# metercam.net
KiCad netlist of a schematic drawn in EAGLE
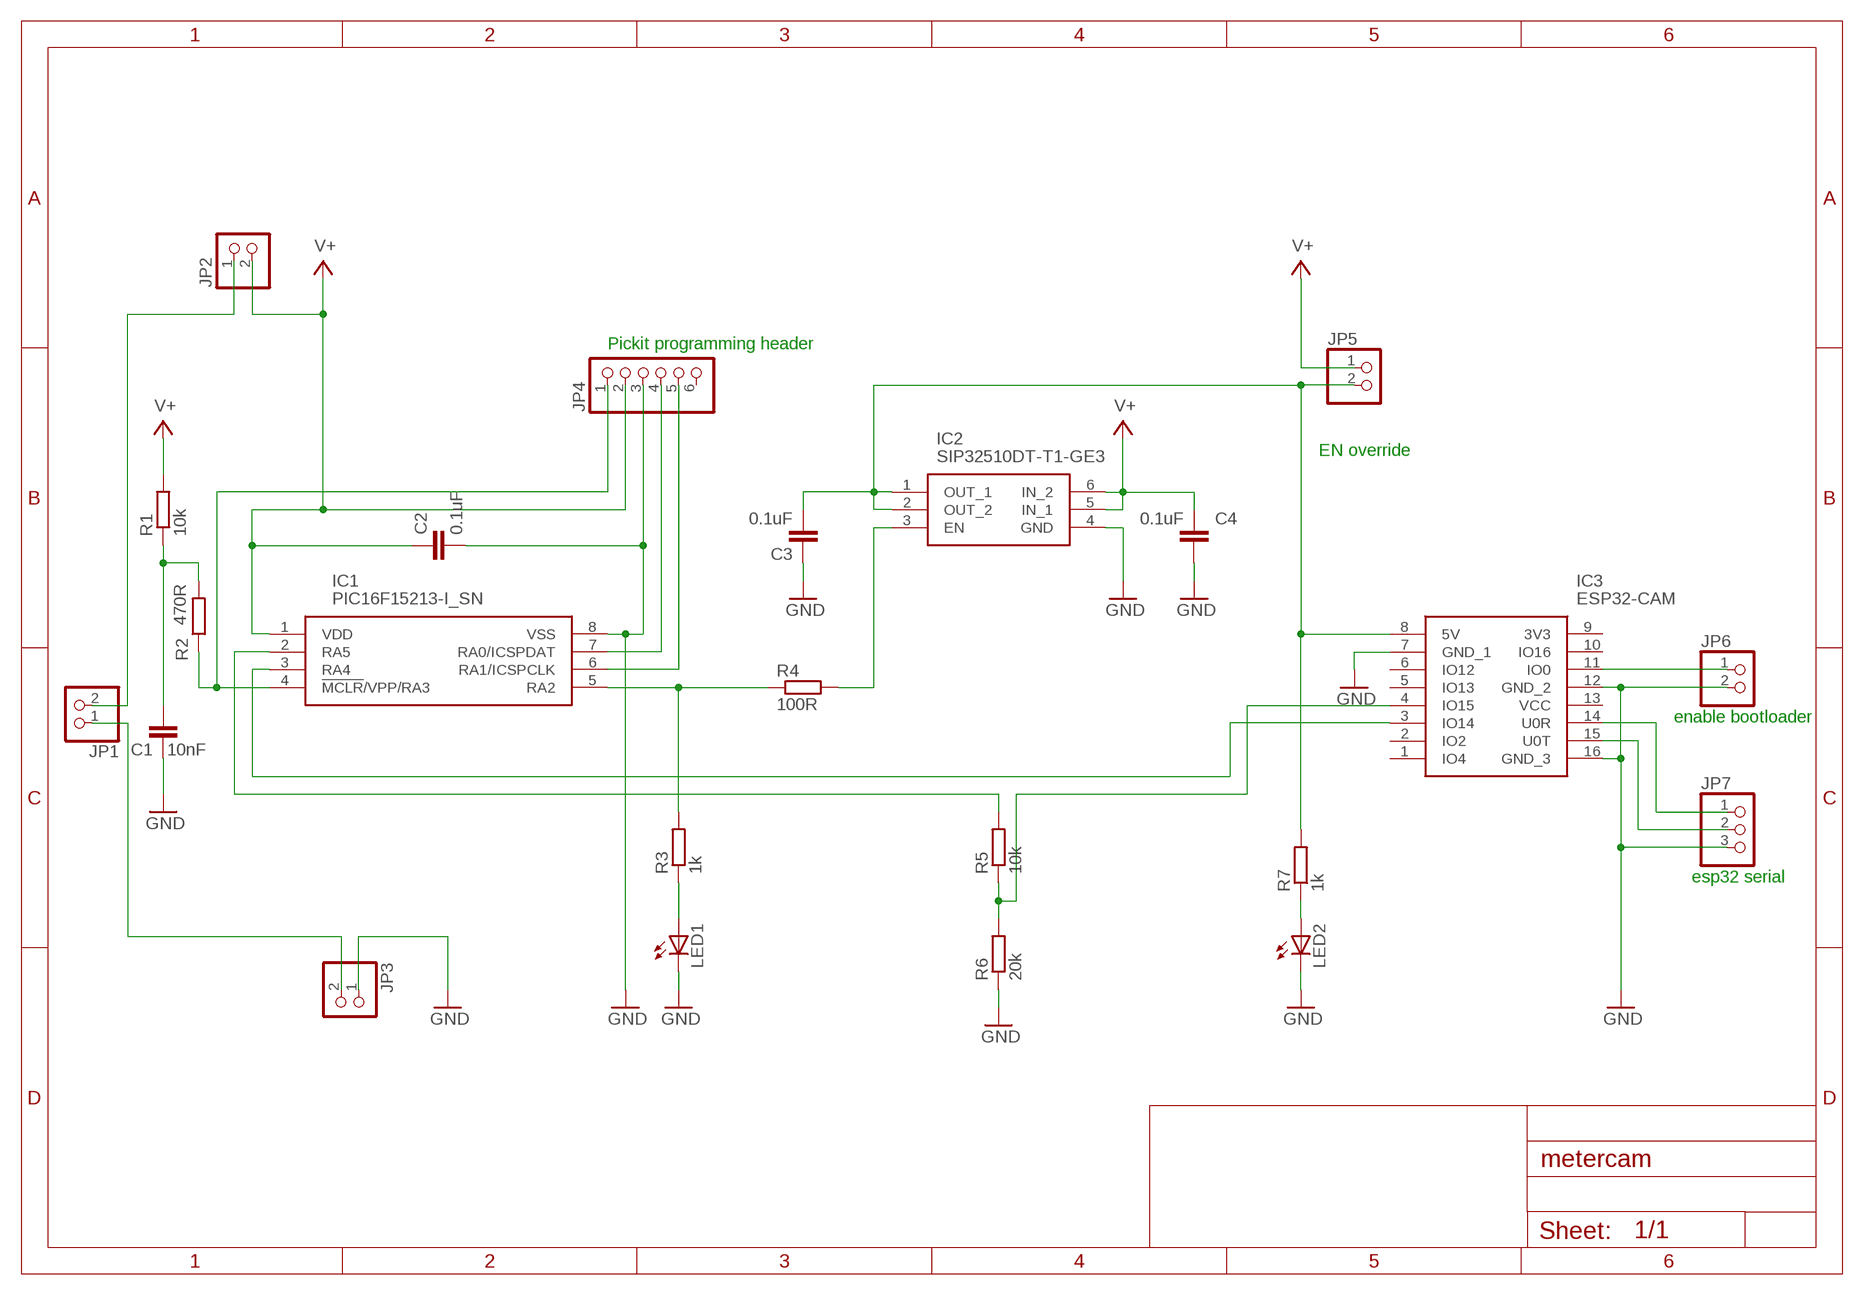
[diagram p0: schematic, sheet 1]

(export (version "E")
  (design (tool "Eeschema 10.0.6"))
  (components
    (comp (ref "C1")
      (value "10nF")
      (footprint "eagle-import:C0805")
      (libsource (lib "eagle-import") (part "C-EUC0805"))
    )
    (comp (ref "C2")
      (value "0.1uF")
      (footprint "eagle-import:C0805")
      (libsource (lib "eagle-import") (part "C-EUC0805"))
    )
    (comp (ref "C3")
      (value "0.1uF")
      (footprint "eagle-import:C0805")
      (libsource (lib "eagle-import") (part "C-EUC0805"))
    )
    (comp (ref "C4")
      (value "0.1uF")
      (footprint "eagle-import:C0805")
      (libsource (lib "eagle-import") (part "C-EUC0805"))
    )
    (comp (ref "IC1")
      (value "PIC16F15213-I_SN")
      (footprint "eagle-import:SOIC127P600X175-8N")
      (fields
        (field (name "MANUFACTURER_PART_NUMBER") "PIC16F15213-I/SN")
        (field (name "MOUSER_PART_NUMBER") "579-PIC16F15213-I/SN")
      )
      (libsource (lib "eagle-import") (part "PIC16F15213-I_SN"))
    )
    (comp (ref "IC2")
      (value "SIP32510DT-T1-GE3")
      (footprint "eagle-import:SOT95P284X110-6N")
      (fields (field (name "MOUSER_PART_NUMBER") "78-SIP32510DT-T1-GE3"))
      (libsource (lib "eagle-import") (part "SIP32510DT-T1-GE3"))
    )
    (comp (ref "IC3")
      (value "ESP32-CAM")
      (footprint "eagle-import:ESP32CAM")
      (libsource (lib "eagle-import") (part "ESP32-CAM"))
    )
    (comp (ref "JP1")
      (value "PINHD-1X2")
      (footprint "eagle-import:1X02")
      (libsource (lib "eagle-import") (part "PINHD-1X2"))
    )
    (comp (ref "JP2")
      (value "PINHD-1X2")
      (footprint "eagle-import:1X02")
      (libsource (lib "eagle-import") (part "PINHD-1X2"))
    )
    (comp (ref "JP3")
      (value "PINHD-1X2")
      (footprint "eagle-import:1X02")
      (libsource (lib "eagle-import") (part "PINHD-1X2"))
    )
    (comp (ref "JP4")
      (value "PINHD-1X6")
      (footprint "eagle-import:1X06")
      (libsource (lib "eagle-import") (part "PINHD-1X6"))
    )
    (comp (ref "JP5")
      (value "PINHD-1X2")
      (footprint "eagle-import:1X02")
      (libsource (lib "eagle-import") (part "PINHD-1X2"))
    )
    (comp (ref "JP6")
      (value "PINHD-1X2")
      (footprint "eagle-import:1X02")
      (libsource (lib "eagle-import") (part "PINHD-1X2"))
    )
    (comp (ref "JP7")
      (value "PINHD-1X3")
      (footprint "eagle-import:1X03")
      (libsource (lib "eagle-import") (part "PINHD-1X3"))
    )
    (comp (ref "LED1")
      (value "LEDSML0805")
      (footprint "eagle-import:SML0805")
      (libsource (lib "eagle-import") (part "LEDSML0805"))
    )
    (comp (ref "LED2")
      (value "LEDSML0805")
      (footprint "eagle-import:SML0805")
      (libsource (lib "eagle-import") (part "LEDSML0805"))
    )
    (comp (ref "R1")
      (value "10k")
      (footprint "eagle-import:R0805")
      (libsource (lib "eagle-import") (part "R-EU_R0805"))
    )
    (comp (ref "R2")
      (value "470R")
      (footprint "eagle-import:R0805")
      (libsource (lib "eagle-import") (part "R-EU_R0805"))
    )
    (comp (ref "R3")
      (value "1k")
      (footprint "eagle-import:R0805")
      (libsource (lib "eagle-import") (part "R-EU_R0805"))
    )
    (comp (ref "R4")
      (value "100R")
      (footprint "eagle-import:R0805")
      (libsource (lib "eagle-import") (part "R-EU_R0805"))
    )
    (comp (ref "R5")
      (value "10k")
      (footprint "eagle-import:R0805")
      (libsource (lib "eagle-import") (part "R-EU_R0805"))
    )
    (comp (ref "R6")
      (value "20k")
      (footprint "eagle-import:R0805")
      (libsource (lib "eagle-import") (part "R-EU_R0805"))
    )
    (comp (ref "R7")
      (value "1k")
      (footprint "eagle-import:R0805")
      (libsource (lib "eagle-import") (part "R-EU_R0805"))
    )
  )
  (nets
    (net (code "1") (name "GND") (class "Default")
      (node (ref "C1") (pin "1") (pinfunction "1_1") (pintype "passive"))
      (node (ref "C2") (pin "2") (pinfunction "2_2") (pintype "passive"))
      (node (ref "C3") (pin "1") (pinfunction "1_1") (pintype "passive"))
      (node (ref "C4") (pin "1") (pinfunction "1_1") (pintype "passive"))
      (node (ref "IC1") (pin "8") (pinfunction "VSS_8") (pintype "bidirectional"))
      (node (ref "IC2") (pin "4") (pinfunction "GND_4") (pintype "bidirectional"))
      (node (ref "IC3") (pin "12") (pinfunction "GND_2_12") (pintype "bidirectional"))
      (node (ref "IC3") (pin "16") (pinfunction "GND_3_16") (pintype "bidirectional"))
      (node (ref "IC3") (pin "7") (pinfunction "GND_1_7") (pintype "bidirectional"))
      (node (ref "JP3") (pin "1") (pinfunction "1_1") (pintype "passive"))
      (node (ref "JP4") (pin "3") (pinfunction "3_3") (pintype "passive"))
      (node (ref "JP6") (pin "2") (pinfunction "2_2") (pintype "passive"))
      (node (ref "JP7") (pin "3") (pinfunction "3_3") (pintype "passive"))
      (node (ref "LED1") (pin "C") (pinfunction "C_C") (pintype "passive"))
      (node (ref "LED2") (pin "C") (pinfunction "C_C") (pintype "passive"))
      (node (ref "R6") (pin "1") (pinfunction "1_1") (pintype "passive"))
    )
    (net (code "2") (name "Net-(C1-Pad2)") (class "Default")
      (node (ref "C1") (pin "2") (pinfunction "2_2") (pintype "passive"))
      (node (ref "R1") (pin "1") (pinfunction "1_1") (pintype "passive"))
      (node (ref "R2") (pin "2") (pinfunction "2_2") (pintype "passive"))
    )
    (net (code "3") (name "Net-(IC1-RA0{slash}ICSPDAT)") (class "Default")
      (node (ref "IC1") (pin "7") (pinfunction "RA0/ICSPDAT_7") (pintype "bidirectional"))
      (node (ref "JP4") (pin "4") (pinfunction "4_4") (pintype "passive"))
    )
    (net (code "4") (name "Net-(IC1-RA1{slash}ICSPCLK)") (class "Default")
      (node (ref "IC1") (pin "6") (pinfunction "RA1/ICSPCLK_6") (pintype "bidirectional"))
      (node (ref "JP4") (pin "5") (pinfunction "5_5") (pintype "passive"))
    )
    (net (code "5") (name "Net-(IC1-RA2)") (class "Default")
      (node (ref "IC1") (pin "5") (pinfunction "RA2_5") (pintype "bidirectional"))
      (node (ref "R3") (pin "2") (pinfunction "2_2") (pintype "passive"))
      (node (ref "R4") (pin "1") (pinfunction "1_1") (pintype "passive"))
    )
    (net (code "6") (name "Net-(IC1-RA4)") (class "Default")
      (node (ref "IC1") (pin "3") (pinfunction "RA4_3") (pintype "bidirectional"))
      (node (ref "IC3") (pin "3") (pinfunction "IO14_3") (pintype "bidirectional"))
    )
    (net (code "7") (name "Net-(IC1-RA5)") (class "Default")
      (node (ref "IC1") (pin "2") (pinfunction "RA5_2") (pintype "bidirectional"))
      (node (ref "R5") (pin "2") (pinfunction "2_2") (pintype "passive"))
    )
    (net (code "8") (name "Net-(IC1-~{MCLR}{slash}VPP{slash}RA3)") (class "Default")
      (node (ref "IC1") (pin "4") (pinfunction "~{MCLR}/VPP/RA3_4") (pintype "bidirectional"))
      (node (ref "JP4") (pin "1") (pinfunction "1_1") (pintype "passive"))
      (node (ref "R2") (pin "1") (pinfunction "1_1") (pintype "passive"))
    )
    (net (code "9") (name "Net-(IC2-EN)") (class "Default")
      (node (ref "IC2") (pin "3") (pinfunction "EN_3") (pintype "bidirectional"))
      (node (ref "R4") (pin "2") (pinfunction "2_2") (pintype "passive"))
    )
    (net (code "10") (name "Net-(IC2-OUT_1)") (class "Default")
      (node (ref "C3") (pin "2") (pinfunction "2_2") (pintype "passive"))
      (node (ref "IC2") (pin "1") (pinfunction "OUT_1_1") (pintype "bidirectional"))
      (node (ref "IC2") (pin "2") (pinfunction "OUT_2_2") (pintype "bidirectional"))
      (node (ref "IC3") (pin "8") (pinfunction "5V_8") (pintype "bidirectional"))
      (node (ref "JP5") (pin "2") (pinfunction "2_2") (pintype "passive"))
      (node (ref "R7") (pin "2") (pinfunction "2_2") (pintype "passive"))
    )
    (net (code "11") (name "Net-(IC3-IO0)") (class "Default")
      (node (ref "IC3") (pin "11") (pinfunction "IO0_11") (pintype "bidirectional"))
      (node (ref "JP6") (pin "1") (pinfunction "1_1") (pintype "passive"))
    )
    (net (code "12") (name "Net-(IC3-IO15)") (class "Default")
      (node (ref "IC3") (pin "4") (pinfunction "IO15_4") (pintype "bidirectional"))
      (node (ref "R5") (pin "1") (pinfunction "1_1") (pintype "passive"))
      (node (ref "R6") (pin "2") (pinfunction "2_2") (pintype "passive"))
    )
    (net (code "13") (name "Net-(IC3-U0R)") (class "Default")
      (node (ref "IC3") (pin "14") (pinfunction "U0R_14") (pintype "bidirectional"))
      (node (ref "JP7") (pin "1") (pinfunction "1_1") (pintype "passive"))
    )
    (net (code "14") (name "Net-(IC3-U0T)") (class "Default")
      (node (ref "IC3") (pin "15") (pinfunction "U0T_15") (pintype "bidirectional"))
      (node (ref "JP7") (pin "2") (pinfunction "2_2") (pintype "passive"))
    )
    (net (code "15") (name "Net-(JP1-Pad1)") (class "Default")
      (node (ref "JP1") (pin "1") (pinfunction "1_1") (pintype "passive"))
      (node (ref "JP3") (pin "2") (pinfunction "2_2") (pintype "passive"))
    )
    (net (code "16") (name "Net-(JP1-Pad2)") (class "Default")
      (node (ref "JP1") (pin "2") (pinfunction "2_2") (pintype "passive"))
      (node (ref "JP2") (pin "1") (pinfunction "1_1") (pintype "passive"))
    )
    (net (code "17") (name "Net-(LED1-PadA)") (class "Default")
      (node (ref "LED1") (pin "A") (pinfunction "A_A") (pintype "passive"))
      (node (ref "R3") (pin "1") (pinfunction "1_1") (pintype "passive"))
    )
    (net (code "18") (name "Net-(LED2-PadA)") (class "Default")
      (node (ref "LED2") (pin "A") (pinfunction "A_A") (pintype "passive"))
      (node (ref "R7") (pin "1") (pinfunction "1_1") (pintype "passive"))
    )
    (net (code "19") (name "V+") (class "Default")
      (node (ref "C2") (pin "1") (pinfunction "1_1") (pintype "passive"))
      (node (ref "C4") (pin "2") (pinfunction "2_2") (pintype "passive"))
      (node (ref "IC1") (pin "1") (pinfunction "VDD_1") (pintype "bidirectional"))
      (node (ref "IC2") (pin "5") (pinfunction "IN_1_5") (pintype "bidirectional"))
      (node (ref "IC2") (pin "6") (pinfunction "IN_2_6") (pintype "bidirectional"))
      (node (ref "JP2") (pin "2") (pinfunction "2_2") (pintype "passive"))
      (node (ref "JP4") (pin "2") (pinfunction "2_2") (pintype "passive"))
      (node (ref "JP5") (pin "1") (pinfunction "1_1") (pintype "passive"))
      (node (ref "R1") (pin "2") (pinfunction "2_2") (pintype "passive"))
    )
    (net (code "20") (name "unconnected-(IC3-3V3-Pad9)") (class "Default")
      (node (ref "IC3") (pin "9") (pinfunction "3V3_9") (pintype "bidirectional"))
    )
    (net (code "21") (name "unconnected-(IC3-IO2-Pad2)") (class "Default")
      (node (ref "IC3") (pin "2") (pinfunction "IO2_2") (pintype "bidirectional"))
    )
    (net (code "22") (name "unconnected-(IC3-IO4-Pad1)") (class "Default")
      (node (ref "IC3") (pin "1") (pinfunction "IO4_1") (pintype "bidirectional"))
    )
    (net (code "23") (name "unconnected-(IC3-IO12-Pad6)") (class "Default")
      (node (ref "IC3") (pin "6") (pinfunction "IO12_6") (pintype "bidirectional"))
    )
    (net (code "24") (name "unconnected-(IC3-IO13-Pad5)") (class "Default")
      (node (ref "IC3") (pin "5") (pinfunction "IO13_5") (pintype "bidirectional"))
    )
    (net (code "25") (name "unconnected-(IC3-IO16-Pad10)") (class "Default")
      (node (ref "IC3") (pin "10") (pinfunction "IO16_10") (pintype "bidirectional"))
    )
    (net (code "26") (name "unconnected-(IC3-VCC-Pad13)") (class "Default")
      (node (ref "IC3") (pin "13") (pinfunction "VCC_13") (pintype "bidirectional"))
    )
    (net (code "27") (name "unconnected-(JP4-Pad6)") (class "Default")
      (node (ref "JP4") (pin "6") (pinfunction "6_6") (pintype "passive"))
    )
  )
)
